# CPU_Dev_revB_1.net
KiCad netlist of a schematic drawn in EAGLE
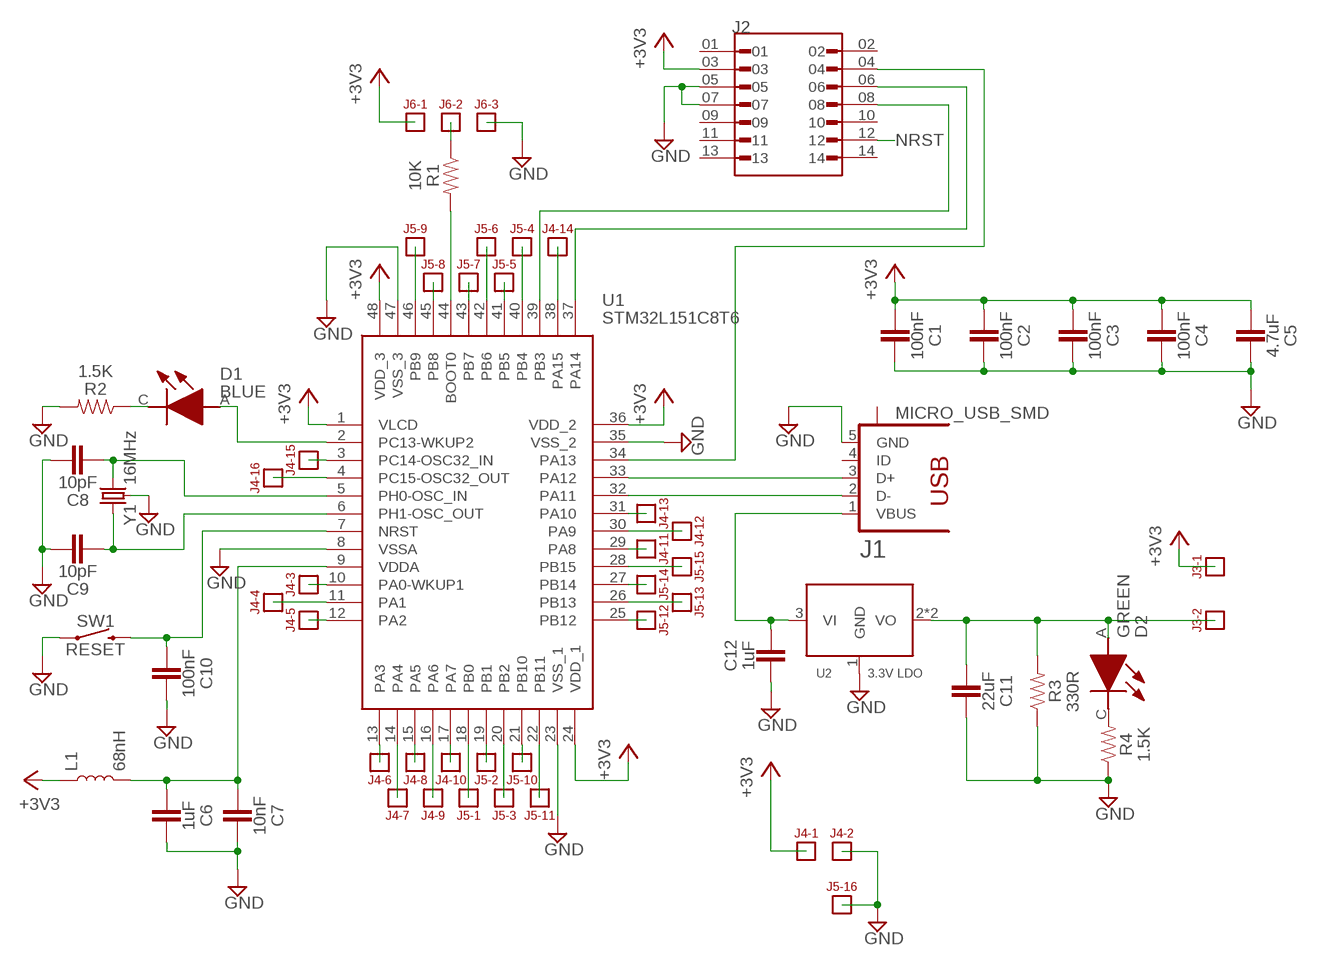
[diagram p0: schematic, sheet 1]

(export (version "E")
  (design (tool "Eeschema 10.0.6"))
  (components
    (comp (ref "C1")
      (value "100nF")
      (footprint "eagle-import:0402")
      (libsource (lib "eagle-import") (part "C_0402"))
    )
    (comp (ref "C2")
      (value "100nF")
      (footprint "eagle-import:0402")
      (libsource (lib "eagle-import") (part "C_0402"))
    )
    (comp (ref "C3")
      (value "100nF")
      (footprint "eagle-import:0402")
      (libsource (lib "eagle-import") (part "C_0402"))
    )
    (comp (ref "C4")
      (value "100nF")
      (footprint "eagle-import:0402")
      (libsource (lib "eagle-import") (part "C_0402"))
    )
    (comp (ref "C5")
      (value "4.7uF")
      (footprint "eagle-import:0402")
      (libsource (lib "eagle-import") (part "C_0402"))
    )
    (comp (ref "C6")
      (value "1uF")
      (footprint "eagle-import:0402")
      (libsource (lib "eagle-import") (part "C_0402"))
    )
    (comp (ref "C7")
      (value "10nF")
      (footprint "eagle-import:0402")
      (libsource (lib "eagle-import") (part "C_0402"))
    )
    (comp (ref "C8")
      (value "10pF")
      (footprint "eagle-import:0402")
      (libsource (lib "eagle-import") (part "C_0402"))
    )
    (comp (ref "C9")
      (value "10pF")
      (footprint "eagle-import:0402")
      (libsource (lib "eagle-import") (part "C_0402"))
    )
    (comp (ref "C10")
      (value "100nF")
      (footprint "eagle-import:0402")
      (libsource (lib "eagle-import") (part "C_0402"))
    )
    (comp (ref "C11")
      (value "22uF")
      (footprint "eagle-import:1206")
      (libsource (lib "eagle-import") (part "C_1206"))
    )
    (comp (ref "C12")
      (value "1uF")
      (footprint "eagle-import:0402")
      (libsource (lib "eagle-import") (part "C_0402"))
    )
    (comp (ref "D1")
      (value "BLUE")
      (footprint "eagle-import:LED_0603")
      (libsource (lib "eagle-import") (part "LED_0603"))
    )
    (comp (ref "D2")
      (value "GREEN")
      (footprint "eagle-import:LED_0603")
      (libsource (lib "eagle-import") (part "LED_0603"))
    )
    (comp (ref "J1")
      (value "MICRO_USB_SMD")
      (footprint "eagle-import:10118192-0002LF")
      (libsource (lib "eagle-import") (part "MICRO_USB_SMD"))
    )
    (comp (ref "J2")
      (value "HEADER_DEBUG_SMD")
      (footprint "eagle-import:HEADER_DEBUG_SMD")
      (libsource (lib "eagle-import") (part "HEADER_DEBUG_SMD"))
    )
    (comp (ref "J3")
      (value "HEADER_2PIN")
      (footprint "eagle-import:HEADER_2PIN")
      (libsource (lib "eagle-import") (part "HEADER_2PIN"))
    )
    (comp (ref "J4")
      (value "HEADER_16PIN")
      (footprint "eagle-import:HEADER_16PIN")
      (libsource (lib "eagle-import") (part "HEADER_16PIN"))
    )
    (comp (ref "J5")
      (value "HEADER_16PIN")
      (footprint "eagle-import:HEADER_16PIN")
      (libsource (lib "eagle-import") (part "HEADER_16PIN"))
    )
    (comp (ref "J6")
      (value "HEADER_3PIN")
      (footprint "eagle-import:HEADER_3PIN")
      (libsource (lib "eagle-import") (part "HEADER_3PIN"))
    )
    (comp (ref "L1")
      (value "68nH")
      (footprint "eagle-import:0603")
      (libsource (lib "eagle-import") (part "L_0603"))
    )
    (comp (ref "R1")
      (value "10K")
      (footprint "eagle-import:0402")
      (libsource (lib "eagle-import") (part "R_0402"))
    )
    (comp (ref "R2")
      (value "1.5K")
      (footprint "eagle-import:0402")
      (libsource (lib "eagle-import") (part "R_0402"))
    )
    (comp (ref "R3")
      (value "330R")
      (footprint "eagle-import:0402")
      (libsource (lib "eagle-import") (part "R_0402"))
    )
    (comp (ref "R4")
      (value "1.5K")
      (footprint "eagle-import:0402")
      (libsource (lib "eagle-import") (part "R_0402"))
    )
    (comp (ref "SW1")
      (value "RESET")
      (footprint "eagle-import:PUSHBUTTON_SMD")
      (libsource (lib "eagle-import") (part "PUSHBUTTON_SMD"))
    )
    (comp (ref "U1")
      (value "STM32L151C8T6")
      (footprint "eagle-import:LQFP-48_7X7")
      (fields (field (name "MOUSER_PART_NUMBER") "511-STM32L151C8T6"))
      (libsource (lib "eagle-import") (part "STM32L151C8T6"))
    )
    (comp (ref "U2")
      (value "3.3V LDO")
      (footprint "eagle-import:SOT223")
      (libsource (lib "eagle-import") (part "VREG_SOT223"))
    )
    (comp (ref "Y1")
      (value "16MHz")
      (footprint "eagle-import:SMD3225-4P")
      (libsource (lib "eagle-import") (part "XTAL_SMD3225-4P"))
    )
  )
  (nets
    (net (code "1") (name "+3V3") (class "Default")
      (node (ref "C1") (pin "1") (pinfunction "1_1") (pintype "passive"))
      (node (ref "C2") (pin "1") (pinfunction "1_1") (pintype "passive"))
      (node (ref "C3") (pin "1") (pinfunction "1_1") (pintype "passive"))
      (node (ref "C4") (pin "1") (pinfunction "1_1") (pintype "passive"))
      (node (ref "C5") (pin "1") (pinfunction "1_1") (pintype "passive"))
      (node (ref "J2") (pin "03") (pinfunction "03_03") (pintype "passive"))
      (node (ref "J3") (pin "P$1") (pinfunction "P$1_P$1") (pintype "bidirectional"))
      (node (ref "J4") (pin "P$1") (pinfunction "P$1_P$1") (pintype "bidirectional"))
      (node (ref "J6") (pin "P$1") (pinfunction "P$1_P$1") (pintype "bidirectional"))
      (node (ref "L1") (pin "1") (pinfunction "1_1") (pintype "passive"))
      (node (ref "U1") (pin "1") (pinfunction "VLCD_1") (pintype "bidirectional"))
      (node (ref "U1") (pin "24") (pinfunction "VDD_1_24") (pintype "bidirectional"))
      (node (ref "U1") (pin "36") (pinfunction "VDD_2_36") (pintype "bidirectional"))
      (node (ref "U1") (pin "48") (pinfunction "VDD_3_48") (pintype "bidirectional"))
    )
    (net (code "2") (name "/NRST") (class "Default")
      (node (ref "C10") (pin "1") (pinfunction "1_1") (pintype "passive"))
      (node (ref "J2") (pin "12") (pinfunction "12_12") (pintype "passive"))
      (node (ref "SW1") (pin "C1") (pinfunction "2_C1") (pintype "passive"))
      (node (ref "SW1") (pin "D1") (pinfunction "2_D1") (pintype "passive"))
      (node (ref "U1") (pin "7") (pinfunction "NRST_7") (pintype "bidirectional"))
    )
    (net (code "3") (name "GND") (class "Default")
      (node (ref "C1") (pin "2") (pinfunction "2_2") (pintype "passive"))
      (node (ref "C10") (pin "2") (pinfunction "2_2") (pintype "passive"))
      (node (ref "C11") (pin "2") (pinfunction "2_2") (pintype "passive"))
      (node (ref "C12") (pin "1") (pinfunction "1_1") (pintype "passive"))
      (node (ref "C2") (pin "2") (pinfunction "2_2") (pintype "passive"))
      (node (ref "C3") (pin "2") (pinfunction "2_2") (pintype "passive"))
      (node (ref "C4") (pin "2") (pinfunction "2_2") (pintype "passive"))
      (node (ref "C5") (pin "2") (pinfunction "2_2") (pintype "passive"))
      (node (ref "C6") (pin "2") (pinfunction "2_2") (pintype "passive"))
      (node (ref "C7") (pin "2") (pinfunction "2_2") (pintype "passive"))
      (node (ref "C8") (pin "2") (pinfunction "2_2") (pintype "passive"))
      (node (ref "C9") (pin "2") (pinfunction "2_2") (pintype "passive"))
      (node (ref "J1") (pin "5") (pinfunction "GND_5") (pintype "passive"))
      (node (ref "J2") (pin "05") (pinfunction "05_05") (pintype "passive"))
      (node (ref "J2") (pin "07") (pinfunction "07_07") (pintype "passive"))
      (node (ref "J4") (pin "P$2") (pinfunction "P$1_P$2") (pintype "bidirectional"))
      (node (ref "J5") (pin "P$16") (pinfunction "P$1_P$16") (pintype "bidirectional"))
      (node (ref "J6") (pin "P$3") (pinfunction "P$1_P$3") (pintype "bidirectional"))
      (node (ref "R2") (pin "2") (pinfunction "2_2") (pintype "passive"))
      (node (ref "R3") (pin "1") (pinfunction "1_1") (pintype "passive"))
      (node (ref "R4") (pin "1") (pinfunction "1_1") (pintype "passive"))
      (node (ref "SW1") (pin "A1") (pinfunction "1_A1") (pintype "passive"))
      (node (ref "SW1") (pin "B1") (pinfunction "1_B1") (pintype "passive"))
      (node (ref "U1") (pin "23") (pinfunction "VSS_1_23") (pintype "bidirectional"))
      (node (ref "U1") (pin "35") (pinfunction "VSS_2_35") (pintype "bidirectional"))
      (node (ref "U1") (pin "47") (pinfunction "VSS_3_47") (pintype "bidirectional"))
      (node (ref "U1") (pin "8") (pinfunction "VSSA_8") (pintype "bidirectional"))
      (node (ref "U2") (pin "1") (pinfunction "GND_1") (pintype "bidirectional"))
      (node (ref "Y1") (pin "2") (pinfunction "3_2") (pintype "passive"))
      (node (ref "Y1") (pin "4") (pinfunction "3_4") (pintype "passive"))
    )
    (net (code "4") (name "Net-(D1-K)") (class "Default")
      (node (ref "D1") (pin "C") (pinfunction "K_C") (pintype "bidirectional"))
      (node (ref "R2") (pin "1") (pinfunction "1_1") (pintype "passive"))
    )
    (net (code "5") (name "Net-(D2-K)") (class "Default")
      (node (ref "D2") (pin "C") (pinfunction "K_C") (pintype "bidirectional"))
      (node (ref "R4") (pin "2") (pinfunction "2_2") (pintype "passive"))
    )
    (net (code "6") (name "Net-(J1-D+)") (class "Default")
      (node (ref "J1") (pin "3") (pinfunction "D+_3") (pintype "passive"))
      (node (ref "U1") (pin "33") (pinfunction "PA12_33") (pintype "bidirectional"))
    )
    (net (code "7") (name "Net-(J1-D-)") (class "Default")
      (node (ref "J1") (pin "2") (pinfunction "D-_2") (pintype "passive"))
      (node (ref "U1") (pin "32") (pinfunction "PA11_32") (pintype "bidirectional"))
    )
    (net (code "8") (name "Net-(J1-VBUS)") (class "Default")
      (node (ref "C12") (pin "2") (pinfunction "2_2") (pintype "passive"))
      (node (ref "J1") (pin "1") (pinfunction "VBUS_1") (pintype "passive"))
      (node (ref "U2") (pin "3") (pinfunction "VI_3") (pintype "bidirectional"))
    )
    (net (code "9") (name "Net-(J3B-P$1)") (class "Default")
      (node (ref "C11") (pin "1") (pinfunction "1_1") (pintype "passive"))
      (node (ref "D2") (pin "A") (pinfunction "A_A") (pintype "bidirectional"))
      (node (ref "J3") (pin "P$2") (pinfunction "P$1_P$2") (pintype "bidirectional"))
      (node (ref "R3") (pin "2") (pinfunction "2_2") (pintype "passive"))
      (node (ref "U2") (pin "2") (pinfunction "VO_2") (pintype "bidirectional"))
      (node (ref "U2") (pin "4") (pinfunction "VO_4") (pintype "bidirectional"))
    )
    (net (code "10") (name "Net-(J4B-P$1)") (class "Default")
      (node (ref "J4") (pin "P$10") (pinfunction "P$1_P$10") (pintype "bidirectional"))
      (node (ref "U1") (pin "17") (pinfunction "PA7_17") (pintype "bidirectional"))
    )
    (net (code "11") (name "Net-(J4C-P$1)") (class "Default")
      (node (ref "J4") (pin "P$11") (pinfunction "P$1_P$11") (pintype "bidirectional"))
      (node (ref "U1") (pin "29") (pinfunction "PA8_29") (pintype "bidirectional"))
    )
    (net (code "12") (name "Net-(J4D-P$1)") (class "Default")
      (node (ref "J4") (pin "P$12") (pinfunction "P$1_P$12") (pintype "bidirectional"))
      (node (ref "U1") (pin "30") (pinfunction "PA9_30") (pintype "bidirectional"))
    )
    (net (code "13") (name "Net-(J4E-P$1)") (class "Default")
      (node (ref "J4") (pin "P$13") (pinfunction "P$1_P$13") (pintype "bidirectional"))
      (node (ref "U1") (pin "31") (pinfunction "PA10_31") (pintype "bidirectional"))
    )
    (net (code "14") (name "Net-(J4F-P$1)") (class "Default")
      (node (ref "J4") (pin "P$14") (pinfunction "P$1_P$14") (pintype "bidirectional"))
      (node (ref "U1") (pin "38") (pinfunction "PA15_38") (pintype "bidirectional"))
    )
    (net (code "15") (name "Net-(J4G-P$1)") (class "Default")
      (node (ref "J4") (pin "P$15") (pinfunction "P$1_P$15") (pintype "bidirectional"))
      (node (ref "U1") (pin "3") (pinfunction "PC14-OSC32_IN_3") (pintype "bidirectional"))
    )
    (net (code "16") (name "Net-(J4H-P$1)") (class "Default")
      (node (ref "J4") (pin "P$16") (pinfunction "P$1_P$16") (pintype "bidirectional"))
      (node (ref "U1") (pin "4") (pinfunction "PC15-OSC32_OUT_4") (pintype "bidirectional"))
    )
    (net (code "17") (name "Net-(J4J-P$1)") (class "Default")
      (node (ref "J4") (pin "P$3") (pinfunction "P$1_P$3") (pintype "bidirectional"))
      (node (ref "U1") (pin "10") (pinfunction "PA0-WKUP1_10") (pintype "bidirectional"))
    )
    (net (code "18") (name "Net-(J4K-P$1)") (class "Default")
      (node (ref "J4") (pin "P$4") (pinfunction "P$1_P$4") (pintype "bidirectional"))
      (node (ref "U1") (pin "11") (pinfunction "PA1_11") (pintype "bidirectional"))
    )
    (net (code "19") (name "Net-(J4L-P$1)") (class "Default")
      (node (ref "J4") (pin "P$5") (pinfunction "P$1_P$5") (pintype "bidirectional"))
      (node (ref "U1") (pin "12") (pinfunction "PA2_12") (pintype "bidirectional"))
    )
    (net (code "20") (name "Net-(J4M-P$1)") (class "Default")
      (node (ref "J4") (pin "P$6") (pinfunction "P$1_P$6") (pintype "bidirectional"))
      (node (ref "U1") (pin "13") (pinfunction "PA3_13") (pintype "bidirectional"))
    )
    (net (code "21") (name "Net-(J4N-P$1)") (class "Default")
      (node (ref "J4") (pin "P$7") (pinfunction "P$1_P$7") (pintype "bidirectional"))
      (node (ref "U1") (pin "14") (pinfunction "PA4_14") (pintype "bidirectional"))
    )
    (net (code "22") (name "Net-(J4O-P$1)") (class "Default")
      (node (ref "J4") (pin "P$8") (pinfunction "P$1_P$8") (pintype "bidirectional"))
      (node (ref "U1") (pin "15") (pinfunction "PA5_15") (pintype "bidirectional"))
    )
    (net (code "23") (name "Net-(J4P-P$1)") (class "Default")
      (node (ref "J4") (pin "P$9") (pinfunction "P$1_P$9") (pintype "bidirectional"))
      (node (ref "U1") (pin "16") (pinfunction "PA6_16") (pintype "bidirectional"))
    )
    (net (code "24") (name "Net-(J5B-P$1)") (class "Default")
      (node (ref "J5") (pin "P$10") (pinfunction "P$1_P$10") (pintype "bidirectional"))
      (node (ref "U1") (pin "21") (pinfunction "PB10_21") (pintype "bidirectional"))
    )
    (net (code "25") (name "Net-(J5C-P$1)") (class "Default")
      (node (ref "J5") (pin "P$11") (pinfunction "P$1_P$11") (pintype "bidirectional"))
      (node (ref "U1") (pin "22") (pinfunction "PB11_22") (pintype "bidirectional"))
    )
    (net (code "26") (name "Net-(J5D-P$1)") (class "Default")
      (node (ref "J5") (pin "P$12") (pinfunction "P$1_P$12") (pintype "bidirectional"))
      (node (ref "U1") (pin "25") (pinfunction "PB12_25") (pintype "bidirectional"))
    )
    (net (code "27") (name "Net-(J5E-P$1)") (class "Default")
      (node (ref "J5") (pin "P$13") (pinfunction "P$1_P$13") (pintype "bidirectional"))
      (node (ref "U1") (pin "26") (pinfunction "PB13_26") (pintype "bidirectional"))
    )
    (net (code "28") (name "Net-(J5F-P$1)") (class "Default")
      (node (ref "J5") (pin "P$14") (pinfunction "P$1_P$14") (pintype "bidirectional"))
      (node (ref "U1") (pin "27") (pinfunction "PB14_27") (pintype "bidirectional"))
    )
    (net (code "29") (name "Net-(J5G-P$1)") (class "Default")
      (node (ref "J5") (pin "P$15") (pinfunction "P$1_P$15") (pintype "bidirectional"))
      (node (ref "U1") (pin "28") (pinfunction "PB15_28") (pintype "bidirectional"))
    )
    (net (code "30") (name "Net-(J5I-P$1)") (class "Default")
      (node (ref "J5") (pin "P$2") (pinfunction "P$1_P$2") (pintype "bidirectional"))
      (node (ref "U1") (pin "19") (pinfunction "PB1_19") (pintype "bidirectional"))
    )
    (net (code "31") (name "Net-(J5J-P$1)") (class "Default")
      (node (ref "J5") (pin "P$3") (pinfunction "P$1_P$3") (pintype "bidirectional"))
      (node (ref "U1") (pin "20") (pinfunction "PB2_20") (pintype "bidirectional"))
    )
    (net (code "32") (name "Net-(J5K-P$1)") (class "Default")
      (node (ref "J5") (pin "P$4") (pinfunction "P$1_P$4") (pintype "bidirectional"))
      (node (ref "U1") (pin "40") (pinfunction "PB4_40") (pintype "bidirectional"))
    )
    (net (code "33") (name "Net-(J5L-P$1)") (class "Default")
      (node (ref "J5") (pin "P$5") (pinfunction "P$1_P$5") (pintype "bidirectional"))
      (node (ref "U1") (pin "41") (pinfunction "PB5_41") (pintype "bidirectional"))
    )
    (net (code "34") (name "Net-(J5M-P$1)") (class "Default")
      (node (ref "J5") (pin "P$6") (pinfunction "P$1_P$6") (pintype "bidirectional"))
      (node (ref "U1") (pin "42") (pinfunction "PB6_42") (pintype "bidirectional"))
    )
    (net (code "35") (name "Net-(J5N-P$1)") (class "Default")
      (node (ref "J5") (pin "P$7") (pinfunction "P$1_P$7") (pintype "bidirectional"))
      (node (ref "U1") (pin "43") (pinfunction "PB7_43") (pintype "bidirectional"))
    )
    (net (code "36") (name "Net-(J5O-P$1)") (class "Default")
      (node (ref "J5") (pin "P$8") (pinfunction "P$1_P$8") (pintype "bidirectional"))
      (node (ref "U1") (pin "45") (pinfunction "PB8_45") (pintype "bidirectional"))
    )
    (net (code "37") (name "Net-(J5P-P$1)") (class "Default")
      (node (ref "J5") (pin "P$9") (pinfunction "P$1_P$9") (pintype "bidirectional"))
      (node (ref "U1") (pin "46") (pinfunction "PB9_46") (pintype "bidirectional"))
    )
    (net (code "38") (name "Net-(J6B-P$1)") (class "Default")
      (node (ref "J6") (pin "P$2") (pinfunction "P$1_P$2") (pintype "bidirectional"))
      (node (ref "R1") (pin "1") (pinfunction "1_1") (pintype "passive"))
    )
    (net (code "39") (name "Net-(U1-BOOT0)") (class "Default")
      (node (ref "R1") (pin "2") (pinfunction "2_2") (pintype "passive"))
      (node (ref "U1") (pin "44") (pinfunction "BOOT0_44") (pintype "bidirectional"))
    )
    (net (code "40") (name "Net-(U1-PA13)") (class "Default")
      (node (ref "J2") (pin "04") (pinfunction "04_04") (pintype "passive"))
      (node (ref "U1") (pin "34") (pinfunction "PA13_34") (pintype "bidirectional"))
    )
    (net (code "41") (name "Net-(U1-PA14)") (class "Default")
      (node (ref "J2") (pin "06") (pinfunction "06_06") (pintype "passive"))
      (node (ref "U1") (pin "37") (pinfunction "PA14_37") (pintype "bidirectional"))
    )
    (net (code "42") (name "Net-(U1-PB0)") (class "Default")
      (node (ref "J5") (pin "P$1") (pinfunction "P$1_P$1") (pintype "bidirectional"))
      (node (ref "U1") (pin "18") (pinfunction "PB0_18") (pintype "bidirectional"))
    )
    (net (code "43") (name "Net-(U1-PB3)") (class "Default")
      (node (ref "J2") (pin "08") (pinfunction "08_08") (pintype "passive"))
      (node (ref "U1") (pin "39") (pinfunction "PB3_39") (pintype "bidirectional"))
    )
    (net (code "44") (name "Net-(U1-PC13-WKUP2)") (class "Default")
      (node (ref "D1") (pin "A") (pinfunction "A_A") (pintype "bidirectional"))
      (node (ref "U1") (pin "2") (pinfunction "PC13-WKUP2_2") (pintype "bidirectional"))
    )
    (net (code "45") (name "Net-(U1-PH0-OSC_IN)") (class "Default")
      (node (ref "C8") (pin "1") (pinfunction "1_1") (pintype "passive"))
      (node (ref "U1") (pin "5") (pinfunction "PH0-OSC_IN_5") (pintype "bidirectional"))
      (node (ref "Y1") (pin "3") (pinfunction "2_3") (pintype "passive"))
    )
    (net (code "46") (name "Net-(U1-PH1-OSC_OUT)") (class "Default")
      (node (ref "C9") (pin "1") (pinfunction "1_1") (pintype "passive"))
      (node (ref "U1") (pin "6") (pinfunction "PH1-OSC_OUT_6") (pintype "bidirectional"))
      (node (ref "Y1") (pin "1") (pinfunction "1_1") (pintype "passive"))
    )
    (net (code "47") (name "Net-(U1-VDDA)") (class "Default")
      (node (ref "C6") (pin "1") (pinfunction "1_1") (pintype "passive"))
      (node (ref "C7") (pin "1") (pinfunction "1_1") (pintype "passive"))
      (node (ref "L1") (pin "2") (pinfunction "2_2") (pintype "passive"))
      (node (ref "U1") (pin "9") (pinfunction "VDDA_9") (pintype "bidirectional"))
    )
    (net (code "48") (name "unconnected-(J1-ID-Pad4)") (class "Default")
      (node (ref "J1") (pin "4") (pinfunction "ID_4") (pintype "passive"))
    )
    (net (code "49") (name "unconnected-(J1-PadS1)") (class "Default")
      (node (ref "J1") (pin "S1") (pinfunction "S1_S1") (pintype "passive"))
    )
    (net (code "50") (name "unconnected-(J2-Pad01)") (class "Default")
      (node (ref "J2") (pin "01") (pinfunction "01_01") (pintype "passive"))
    )
    (net (code "51") (name "unconnected-(J2-Pad02)") (class "Default")
      (node (ref "J2") (pin "02") (pinfunction "02_02") (pintype "passive"))
    )
    (net (code "52") (name "unconnected-(J2-Pad09)") (class "Default")
      (node (ref "J2") (pin "09") (pinfunction "09_09") (pintype "passive"))
    )
    (net (code "53") (name "unconnected-(J2-Pad10)") (class "Default")
      (node (ref "J2") (pin "10") (pinfunction "10_10") (pintype "passive"))
    )
    (net (code "54") (name "unconnected-(J2-Pad11)") (class "Default")
      (node (ref "J2") (pin "11") (pinfunction "11_11") (pintype "passive"))
    )
    (net (code "55") (name "unconnected-(J2-Pad13)") (class "Default")
      (node (ref "J2") (pin "13") (pinfunction "13_13") (pintype "passive"))
    )
    (net (code "56") (name "unconnected-(J2-Pad14)") (class "Default")
      (node (ref "J2") (pin "14") (pinfunction "14_14") (pintype "passive"))
    )
  )
)
